# LDO.net
KiCad netlist of a schematic drawn in Altium Designer
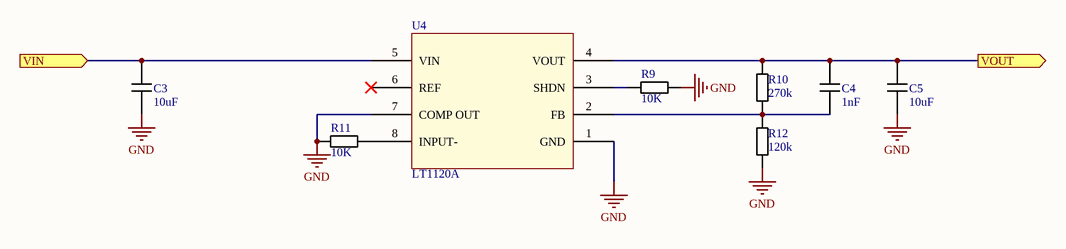
[diagram p0: LDO.SchDoc]

(export (version "E")
  (design (tool "Eeschema 10.0.6"))
  (components
    (comp (ref "C3")
      (value "10uF")
      (footprint "0805 Cap")
      (description "0805 MLCC - NP0, 5%")
      (fields (field (name "Comment") "0805 Cap"))
      (libsource (lib "Schlib1") (part "0805 MLCC - NP0, 5%"))
    )
    (comp (ref "C4")
      (value "1nF")
      (footprint "0805 Cap")
      (description "0805 MLCC - NP0, 5%")
      (fields (field (name "Comment") "0805 Cap"))
      (libsource (lib "Schlib1") (part "0805 MLCC - NP0, 5%"))
    )
    (comp (ref "C5")
      (value "10uF")
      (footprint "0805 Cap")
      (description "0805 MLCC - NP0, 5%")
      (fields (field (name "Comment") "0805 Cap"))
      (libsource (lib "Schlib1") (part "0805 MLCC - NP0, 5%"))
    )
    (comp (ref "R9")
      (value "10K")
      (footprint "0805 Resistor")
      (description "0805 Thick Film Resistor 1%")
      (fields (field (name "Comment") "0805 Resistor"))
      (libsource (lib "") (part "0805 Thick Film Resistor 1%_1"))
    )
    (comp (ref "R10")
      (value "270k")
      (footprint "0805 Resistor")
      (description "0805 Thick Film Resistor 1%")
      (fields (field (name "Comment") "0805 Resistor"))
      (libsource (lib "Schlib1") (part "0805 Thick Film Resistor 1%"))
    )
    (comp (ref "R11")
      (value "10K")
      (footprint "0805 Resistor")
      (description "0805 Thick Film Resistor 1%")
      (fields (field (name "Comment") "0805 Resistor"))
      (libsource (lib "") (part "0805 Thick Film Resistor 1%_1"))
    )
    (comp (ref "R12")
      (value "120k")
      (footprint "0805 Resistor")
      (description "0805 Thick Film Resistor 1%")
      (fields (field (name "Comment") "0805 Resistor"))
      (libsource (lib "Schlib1") (part "0805 Thick Film Resistor 1%"))
    )
    (comp (ref "U4")
      (value "LT1120A")
      (footprint "SOIC8 - LT1120A")
      (description "Low Dropout Regulator")
      (libsource (lib "Schlib1") (part "LT1120A"))
    )
  )
  (nets
    (net (code "1") (name "/VIN") (class "Default")
      (node (ref "C3") (pin "2") (pinfunction "2_2") (pintype "passive"))
      (node (ref "U4") (pin "5") (pinfunction "VIN_5") (pintype "passive"))
    )
    (net (code "2") (name "/VOUT") (class "Default")
      (node (ref "C4") (pin "2") (pinfunction "2_2") (pintype "passive"))
      (node (ref "C5") (pin "2") (pinfunction "2_2") (pintype "passive"))
      (node (ref "R10") (pin "2") (pinfunction "2_2") (pintype "passive"))
      (node (ref "U4") (pin "4") (pinfunction "VOUT_4") (pintype "passive"))
    )
    (net (code "3") (name "GND") (class "Default")
      (node (ref "C3") (pin "1") (pinfunction "1_1") (pintype "passive"))
      (node (ref "C5") (pin "1") (pinfunction "1_1") (pintype "passive"))
      (node (ref "R11") (pin "1") (pinfunction "1_1") (pintype "passive"))
      (node (ref "R12") (pin "1") (pinfunction "1_1") (pintype "passive"))
      (node (ref "R9") (pin "2") (pinfunction "2_2") (pintype "passive"))
      (node (ref "U4") (pin "1") (pinfunction "GND_1") (pintype "passive"))
      (node (ref "U4") (pin "7") (pinfunction "COMP_OUT_7") (pintype "passive"))
    )
    (net (code "4") (name "Net-(U4-FB)") (class "Default")
      (node (ref "C4") (pin "1") (pinfunction "1_1") (pintype "passive"))
      (node (ref "R10") (pin "1") (pinfunction "1_1") (pintype "passive"))
      (node (ref "R12") (pin "2") (pinfunction "2_2") (pintype "passive"))
      (node (ref "U4") (pin "2") (pinfunction "FB_2") (pintype "passive"))
    )
    (net (code "5") (name "Net-(U4-INPUT-)") (class "Default")
      (node (ref "R11") (pin "2") (pinfunction "2_2") (pintype "passive"))
      (node (ref "U4") (pin "8") (pinfunction "INPUT-_8") (pintype "passive"))
    )
    (net (code "6") (name "Net-(U4-SHDN)") (class "Default")
      (node (ref "R9") (pin "1") (pinfunction "1_1") (pintype "passive"))
      (node (ref "U4") (pin "3") (pinfunction "SHDN_3") (pintype "passive"))
    )
    (net (code "7") (name "unconnected-(U4-REF-Pad6)") (class "Default")
      (node (ref "U4") (pin "6") (pinfunction "REF_6") (pintype "passive+no_connect"))
    )
  )
)
